# SSBreakout_Board.net
KiCad netlist of a schematic drawn in Altium Designer
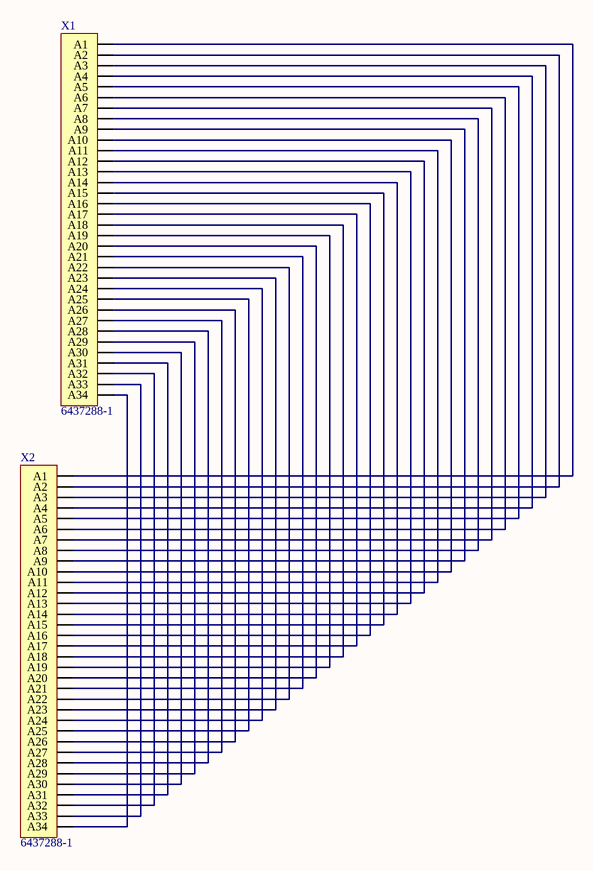
[diagram p0: SSBreakout Board.SchDoc]

(export (version "E")
  (design (tool "Eeschema 10.0.6"))
  (components
    (comp (ref "X1")
      (value "6437288-1")
      (footprint "6437288-1")
      (description "Superseal 34P")
      (libsource (lib "Connectors") (part "6437288-1"))
    )
    (comp (ref "X2")
      (value "6437288-1")
      (footprint "6437288-1")
      (description "Superseal 34P")
      (libsource (lib "Connectors") (part "6437288-1"))
    )
  )
  (nets
    (net (code "1") (name "Net-(X1-PadA1)") (class "Default")
      (node (ref "X1") (pin "A1") (pinfunction "A1_A1") (pintype "passive"))
      (node (ref "X2") (pin "A1") (pinfunction "A1_A1") (pintype "passive"))
    )
    (net (code "2") (name "Net-(X1-PadA2)") (class "Default")
      (node (ref "X1") (pin "A2") (pinfunction "A2_A2") (pintype "passive"))
      (node (ref "X2") (pin "A2") (pinfunction "A2_A2") (pintype "passive"))
    )
    (net (code "3") (name "Net-(X1-PadA3)") (class "Default")
      (node (ref "X1") (pin "A3") (pinfunction "A3_A3") (pintype "passive"))
      (node (ref "X2") (pin "A3") (pinfunction "A3_A3") (pintype "passive"))
    )
    (net (code "4") (name "Net-(X1-PadA4)") (class "Default")
      (node (ref "X1") (pin "A4") (pinfunction "A4_A4") (pintype "passive"))
      (node (ref "X2") (pin "A4") (pinfunction "A4_A4") (pintype "passive"))
    )
    (net (code "5") (name "Net-(X1-PadA5)") (class "Default")
      (node (ref "X1") (pin "A5") (pinfunction "A5_A5") (pintype "passive"))
      (node (ref "X2") (pin "A5") (pinfunction "A5_A5") (pintype "passive"))
    )
    (net (code "6") (name "Net-(X1-PadA6)") (class "Default")
      (node (ref "X1") (pin "A6") (pinfunction "A6_A6") (pintype "passive"))
      (node (ref "X2") (pin "A6") (pinfunction "A6_A6") (pintype "passive"))
    )
    (net (code "7") (name "Net-(X1-PadA7)") (class "Default")
      (node (ref "X1") (pin "A7") (pinfunction "A7_A7") (pintype "passive"))
      (node (ref "X2") (pin "A7") (pinfunction "A7_A7") (pintype "passive"))
    )
    (net (code "8") (name "Net-(X1-PadA8)") (class "Default")
      (node (ref "X1") (pin "A8") (pinfunction "A8_A8") (pintype "passive"))
      (node (ref "X2") (pin "A8") (pinfunction "A8_A8") (pintype "passive"))
    )
    (net (code "9") (name "Net-(X1-PadA9)") (class "Default")
      (node (ref "X1") (pin "A9") (pinfunction "A9_A9") (pintype "passive"))
      (node (ref "X2") (pin "A9") (pinfunction "A9_A9") (pintype "passive"))
    )
    (net (code "10") (name "Net-(X1-PadA10)") (class "Default")
      (node (ref "X1") (pin "A10") (pinfunction "A10_A10") (pintype "passive"))
      (node (ref "X2") (pin "A10") (pinfunction "A10_A10") (pintype "passive"))
    )
    (net (code "11") (name "Net-(X1-PadA11)") (class "Default")
      (node (ref "X1") (pin "A11") (pinfunction "A11_A11") (pintype "passive"))
      (node (ref "X2") (pin "A11") (pinfunction "A11_A11") (pintype "passive"))
    )
    (net (code "12") (name "Net-(X1-PadA12)") (class "Default")
      (node (ref "X1") (pin "A12") (pinfunction "A12_A12") (pintype "passive"))
      (node (ref "X2") (pin "A12") (pinfunction "A12_A12") (pintype "passive"))
    )
    (net (code "13") (name "Net-(X1-PadA13)") (class "Default")
      (node (ref "X1") (pin "A13") (pinfunction "A13_A13") (pintype "passive"))
      (node (ref "X2") (pin "A13") (pinfunction "A13_A13") (pintype "passive"))
    )
    (net (code "14") (name "Net-(X1-PadA14)") (class "Default")
      (node (ref "X1") (pin "A14") (pinfunction "A14_A14") (pintype "passive"))
      (node (ref "X2") (pin "A14") (pinfunction "A14_A14") (pintype "passive"))
    )
    (net (code "15") (name "Net-(X1-PadA15)") (class "Default")
      (node (ref "X1") (pin "A15") (pinfunction "A15_A15") (pintype "passive"))
      (node (ref "X2") (pin "A15") (pinfunction "A15_A15") (pintype "passive"))
    )
    (net (code "16") (name "Net-(X1-PadA16)") (class "Default")
      (node (ref "X1") (pin "A16") (pinfunction "A16_A16") (pintype "passive"))
      (node (ref "X2") (pin "A16") (pinfunction "A16_A16") (pintype "passive"))
    )
    (net (code "17") (name "Net-(X1-PadA17)") (class "Default")
      (node (ref "X1") (pin "A17") (pinfunction "A17_A17") (pintype "passive"))
      (node (ref "X2") (pin "A17") (pinfunction "A17_A17") (pintype "passive"))
    )
    (net (code "18") (name "Net-(X1-PadA18)") (class "Default")
      (node (ref "X1") (pin "A18") (pinfunction "A18_A18") (pintype "passive"))
      (node (ref "X2") (pin "A18") (pinfunction "A18_A18") (pintype "passive"))
    )
    (net (code "19") (name "Net-(X1-PadA19)") (class "Default")
      (node (ref "X1") (pin "A19") (pinfunction "A19_A19") (pintype "passive"))
      (node (ref "X2") (pin "A19") (pinfunction "A19_A19") (pintype "passive"))
    )
    (net (code "20") (name "Net-(X1-PadA20)") (class "Default")
      (node (ref "X1") (pin "A20") (pinfunction "A20_A20") (pintype "passive"))
      (node (ref "X2") (pin "A20") (pinfunction "A20_A20") (pintype "passive"))
    )
    (net (code "21") (name "Net-(X1-PadA21)") (class "Default")
      (node (ref "X1") (pin "A21") (pinfunction "A21_A21") (pintype "passive"))
      (node (ref "X2") (pin "A21") (pinfunction "A21_A21") (pintype "passive"))
    )
    (net (code "22") (name "Net-(X1-PadA22)") (class "Default")
      (node (ref "X1") (pin "A22") (pinfunction "A22_A22") (pintype "passive"))
      (node (ref "X2") (pin "A22") (pinfunction "A22_A22") (pintype "passive"))
    )
    (net (code "23") (name "Net-(X1-PadA23)") (class "Default")
      (node (ref "X1") (pin "A23") (pinfunction "A23_A23") (pintype "passive"))
      (node (ref "X2") (pin "A23") (pinfunction "A23_A23") (pintype "passive"))
    )
    (net (code "24") (name "Net-(X1-PadA24)") (class "Default")
      (node (ref "X1") (pin "A24") (pinfunction "A24_A24") (pintype "passive"))
      (node (ref "X2") (pin "A24") (pinfunction "A24_A24") (pintype "passive"))
    )
    (net (code "25") (name "Net-(X1-PadA25)") (class "Default")
      (node (ref "X1") (pin "A25") (pinfunction "A25_A25") (pintype "passive"))
      (node (ref "X2") (pin "A25") (pinfunction "A25_A25") (pintype "passive"))
    )
    (net (code "26") (name "Net-(X1-PadA26)") (class "Default")
      (node (ref "X1") (pin "A26") (pinfunction "A26_A26") (pintype "passive"))
      (node (ref "X2") (pin "A26") (pinfunction "A26_A26") (pintype "passive"))
    )
    (net (code "27") (name "Net-(X1-PadA27)") (class "Default")
      (node (ref "X1") (pin "A27") (pinfunction "A27_A27") (pintype "passive"))
      (node (ref "X2") (pin "A27") (pinfunction "A27_A27") (pintype "passive"))
    )
    (net (code "28") (name "Net-(X1-PadA28)") (class "Default")
      (node (ref "X1") (pin "A28") (pinfunction "A28_A28") (pintype "passive"))
      (node (ref "X2") (pin "A28") (pinfunction "A28_A28") (pintype "passive"))
    )
    (net (code "29") (name "Net-(X1-PadA29)") (class "Default")
      (node (ref "X1") (pin "A29") (pinfunction "A29_A29") (pintype "passive"))
      (node (ref "X2") (pin "A29") (pinfunction "A29_A29") (pintype "passive"))
    )
    (net (code "30") (name "Net-(X1-PadA30)") (class "Default")
      (node (ref "X1") (pin "A30") (pinfunction "A30_A30") (pintype "passive"))
      (node (ref "X2") (pin "A30") (pinfunction "A30_A30") (pintype "passive"))
    )
    (net (code "31") (name "Net-(X1-PadA31)") (class "Default")
      (node (ref "X1") (pin "A31") (pinfunction "A31_A31") (pintype "passive"))
      (node (ref "X2") (pin "A31") (pinfunction "A31_A31") (pintype "passive"))
    )
    (net (code "32") (name "Net-(X1-PadA32)") (class "Default")
      (node (ref "X1") (pin "A32") (pinfunction "A32_A32") (pintype "passive"))
      (node (ref "X2") (pin "A32") (pinfunction "A32_A32") (pintype "passive"))
    )
    (net (code "33") (name "Net-(X1-PadA33)") (class "Default")
      (node (ref "X1") (pin "A33") (pinfunction "A33_A33") (pintype "passive"))
      (node (ref "X2") (pin "A33") (pinfunction "A33_A33") (pintype "passive"))
    )
    (net (code "34") (name "Net-(X1-PadA34)") (class "Default")
      (node (ref "X1") (pin "A34") (pinfunction "A34_A34") (pintype "passive"))
      (node (ref "X2") (pin "A34") (pinfunction "A34_A34") (pintype "passive"))
    )
  )
)
